# CameraController.net
KiCad netlist of a schematic drawn in EAGLE
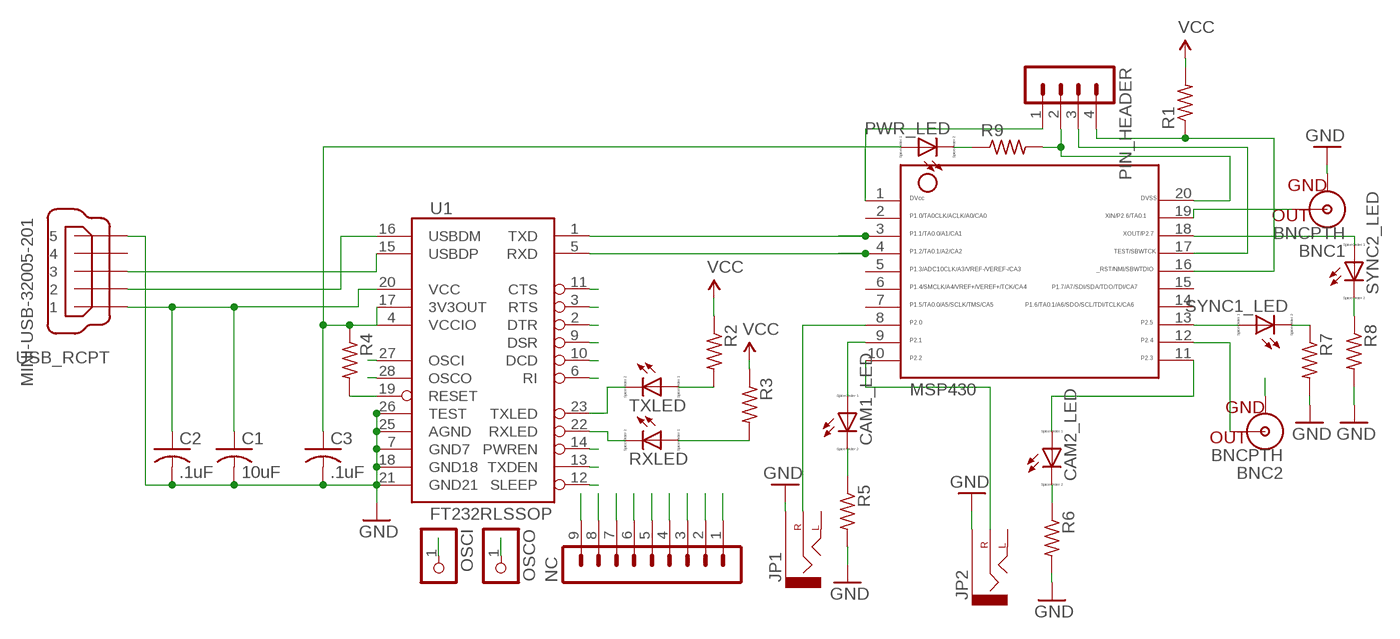
[diagram p0: schematic, sheet 1]

(export (version "E")
  (design (tool "Eeschema 10.0.6"))
  (components
    (comp (ref "BNC1")
      (value "BNCPTH")
      (footprint "eagle-import:BNC")
      (libsource (lib "eagle-import") (part "BNCPTH"))
    )
    (comp (ref "BNC2")
      (value "BNCPTH")
      (footprint "eagle-import:BNC")
      (libsource (lib "eagle-import") (part "BNCPTH"))
    )
    (comp (ref "C1")
      (value "10uF")
      (footprint "eagle-import:C0805")
      (libsource (lib "eagle-import") (part "C-USC0805"))
    )
    (comp (ref "C2")
      (value ".1uF")
      (footprint "eagle-import:C0603")
      (libsource (lib "eagle-import") (part "C-USC0603"))
    )
    (comp (ref "C3")
      (value ".1uF")
      (footprint "eagle-import:C0603")
      (libsource (lib "eagle-import") (part "C-USC0603"))
    )
    (comp (ref "CAM1_LED")
      (value "LED_E")
      (footprint "eagle-import:LED_1206")
      (libsource (lib "eagle-import") (part "LED_E"))
    )
    (comp (ref "CAM2_LED")
      (value "LED_E")
      (footprint "eagle-import:LED_1206")
      (libsource (lib "eagle-import") (part "LED_E"))
    )
    (comp (ref "JP1")
      (value "AUDIO-JACKPTH")
      (footprint "eagle-import:AUDIO-JACK")
      (libsource (lib "eagle-import") (part "AUDIO-JACKPTH"))
    )
    (comp (ref "JP2")
      (value "AUDIO-JACKPTH")
      (footprint "eagle-import:AUDIO-JACK")
      (libsource (lib "eagle-import") (part "AUDIO-JACKPTH"))
    )
    (comp (ref "MSP430")
      (value "MSP430")
      (footprint "eagle-import:20_PIN")
      (libsource (lib "eagle-import") (part "MSP430"))
    )
    (comp (ref "NC")
      (value "MA09-1")
      (footprint "eagle-import:MA09-1")
      (libsource (lib "eagle-import") (part "MA09-1"))
    )
    (comp (ref "OSCI")
      (value "PINHD-1X1")
      (footprint "eagle-import:1X01")
      (libsource (lib "eagle-import") (part "PINHD-1X1"))
    )
    (comp (ref "OSCO")
      (value "PINHD-1X1")
      (footprint "eagle-import:1X01")
      (libsource (lib "eagle-import") (part "PINHD-1X1"))
    )
    (comp (ref "PIN_HEADER")
      (value "MA04-1")
      (footprint "eagle-import:MA04-1")
      (libsource (lib "eagle-import") (part "MA04-1"))
    )
    (comp (ref "PWR_LED")
      (value "LED_E")
      (footprint "eagle-import:LED_1206")
      (libsource (lib "eagle-import") (part "LED_E"))
    )
    (comp (ref "R1")
      (value "R-US_R1206")
      (footprint "eagle-import:R1206")
      (libsource (lib "eagle-import") (part "R-US_R1206"))
    )
    (comp (ref "R2")
      (value "R-US_R1206")
      (footprint "eagle-import:R1206")
      (libsource (lib "eagle-import") (part "R-US_R1206"))
    )
    (comp (ref "R3")
      (value "R-US_R1206")
      (footprint "eagle-import:R1206")
      (libsource (lib "eagle-import") (part "R-US_R1206"))
    )
    (comp (ref "R4")
      (value "R-US_R1206")
      (footprint "eagle-import:R1206")
      (libsource (lib "eagle-import") (part "R-US_R1206"))
    )
    (comp (ref "R5")
      (value "R-US_R1206")
      (footprint "eagle-import:R1206")
      (libsource (lib "eagle-import") (part "R-US_R1206"))
    )
    (comp (ref "R6")
      (value "R-US_R1206")
      (footprint "eagle-import:R1206")
      (libsource (lib "eagle-import") (part "R-US_R1206"))
    )
    (comp (ref "R7")
      (value "R-US_R1206")
      (footprint "eagle-import:R1206")
      (libsource (lib "eagle-import") (part "R-US_R1206"))
    )
    (comp (ref "R8")
      (value "R-US_R1206")
      (footprint "eagle-import:R1206")
      (libsource (lib "eagle-import") (part "R-US_R1206"))
    )
    (comp (ref "R9")
      (value "R-US_R1206")
      (footprint "eagle-import:R1206")
      (libsource (lib "eagle-import") (part "R-US_R1206"))
    )
    (comp (ref "RXLED")
      (value "LED_E")
      (footprint "eagle-import:LED_1206")
      (libsource (lib "eagle-import") (part "LED_E"))
    )
    (comp (ref "SYNC1_LED")
      (value "LED_E")
      (footprint "eagle-import:LED_1206")
      (libsource (lib "eagle-import") (part "LED_E"))
    )
    (comp (ref "SYNC2_LED")
      (value "LED_E")
      (footprint "eagle-import:LED_1206")
      (libsource (lib "eagle-import") (part "LED_E"))
    )
    (comp (ref "TXLED")
      (value "LED_E")
      (footprint "eagle-import:LED_1206")
      (libsource (lib "eagle-import") (part "LED_E"))
    )
    (comp (ref "U1")
      (value "FT232RLSSOP")
      (footprint "eagle-import:SSOP28DB")
      (libsource (lib "eagle-import") (part "FT232RLSSOP"))
    )
    (comp (ref "USB_RCPT")
      (value "MINI-USB-32005-201")
      (footprint "eagle-import:32005-201")
      (libsource (lib "eagle-import") (part "MINI-USB-32005-201"))
    )
  )
  (nets
    (net (code "1") (name "/CTS") (class "Default")
      (node (ref "NC") (pin "4") (pinfunction "4_4") (pintype "passive"))
      (node (ref "U1") (pin "11") (pinfunction "CTS_11") (pintype "input"))
    )
    (net (code "2") (name "/DCD") (class "Default")
      (node (ref "NC") (pin "5") (pinfunction "5_5") (pintype "passive"))
      (node (ref "U1") (pin "10") (pinfunction "DCD_10") (pintype "input"))
    )
    (net (code "3") (name "/DSR") (class "Default")
      (node (ref "NC") (pin "6") (pinfunction "6_6") (pintype "passive"))
      (node (ref "U1") (pin "9") (pinfunction "DSR_9") (pintype "input"))
    )
    (net (code "4") (name "/DTR") (class "Default")
      (node (ref "NC") (pin "9") (pinfunction "9_9") (pintype "passive"))
      (node (ref "U1") (pin "2") (pinfunction "DTR_2") (pintype "output"))
    )
    (net (code "5") (name "/OSCI") (class "Default")
      (node (ref "OSCI") (pin "1") (pinfunction "1_1") (pintype "passive"))
      (node (ref "U1") (pin "27") (pinfunction "OSCI_27") (pintype "input"))
    )
    (net (code "6") (name "/OSCO") (class "Default")
      (node (ref "OSCO") (pin "1") (pinfunction "1_1") (pintype "passive"))
      (node (ref "U1") (pin "28") (pinfunction "OSCO_28") (pintype "output"))
    )
    (net (code "7") (name "/PWREN") (class "Default")
      (node (ref "NC") (pin "1") (pinfunction "1_1") (pintype "passive"))
      (node (ref "U1") (pin "14") (pinfunction "PWREN_14") (pintype "input"))
    )
    (net (code "8") (name "/RI") (class "Default")
      (node (ref "NC") (pin "7") (pinfunction "7_7") (pintype "passive"))
      (node (ref "U1") (pin "6") (pinfunction "RI_6") (pintype "input"))
    )
    (net (code "9") (name "/RTS") (class "Default")
      (node (ref "NC") (pin "8") (pinfunction "8_8") (pintype "passive"))
      (node (ref "U1") (pin "3") (pinfunction "RTS_3") (pintype "output"))
    )
    (net (code "10") (name "/SLEEP") (class "Default")
      (node (ref "NC") (pin "3") (pinfunction "3_3") (pintype "passive"))
      (node (ref "U1") (pin "12") (pinfunction "SLEEP_12") (pintype "input"))
    )
    (net (code "11") (name "/TXDEN") (class "Default")
      (node (ref "NC") (pin "2") (pinfunction "2_2") (pintype "passive"))
      (node (ref "U1") (pin "13") (pinfunction "TXDEN_13") (pintype "input"))
    )
    (net (code "12") (name "GND") (class "Default")
      (node (ref "BNC1") (pin "GND") (pinfunction "GND_GND") (pintype "bidirectional"))
      (node (ref "BNC2") (pin "GND") (pinfunction "GND_GND") (pintype "bidirectional"))
      (node (ref "C1") (pin "2") (pinfunction "2_2") (pintype "passive"))
      (node (ref "C2") (pin "2") (pinfunction "2_2") (pintype "passive"))
      (node (ref "C3") (pin "2") (pinfunction "2_2") (pintype "passive"))
      (node (ref "JP1") (pin "SLEEVE") (pinfunction "SLEEVE_SLEEVE") (pintype "bidirectional"))
      (node (ref "JP2") (pin "SLEEVE") (pinfunction "SLEEVE_SLEEVE") (pintype "bidirectional"))
      (node (ref "MSP430") (pin "20") (pinfunction "20_20") (pintype "bidirectional"))
      (node (ref "PIN_HEADER") (pin "2") (pinfunction "2_2") (pintype "passive"))
      (node (ref "R5") (pin "2") (pinfunction "2_2") (pintype "passive"))
      (node (ref "R6") (pin "2") (pinfunction "2_2") (pintype "passive"))
      (node (ref "R7") (pin "2") (pinfunction "2_2") (pintype "passive"))
      (node (ref "R8") (pin "2") (pinfunction "2_2") (pintype "passive"))
      (node (ref "R9") (pin "2") (pinfunction "2_2") (pintype "passive"))
      (node (ref "U1") (pin "18") (pinfunction "GND18_18") (pintype "power_in"))
      (node (ref "U1") (pin "21") (pinfunction "GND21_21") (pintype "power_in"))
      (node (ref "U1") (pin "25") (pinfunction "AGND_25") (pintype "power_in"))
      (node (ref "U1") (pin "26") (pinfunction "TEST_26") (pintype "input"))
      (node (ref "U1") (pin "7") (pinfunction "GND7_7") (pintype "power_in"))
      (node (ref "USB_RCPT") (pin "5") (pinfunction "5_5") (pintype "passive"))
    )
    (net (code "13") (name "Net-(BNC1-OUT)") (class "Default")
      (node (ref "BNC1") (pin "S") (pinfunction "OUT_S") (pintype "bidirectional"))
      (node (ref "MSP430") (pin "19") (pinfunction "19_19") (pintype "bidirectional"))
    )
    (net (code "14") (name "Net-(BNC2-OUT)") (class "Default")
      (node (ref "BNC2") (pin "S") (pinfunction "OUT_S") (pintype "bidirectional"))
      (node (ref "MSP430") (pin "12") (pinfunction "12_12") (pintype "bidirectional"))
    )
    (net (code "15") (name "Net-(CAM1_LED-PadA)") (class "Default")
      (node (ref "CAM1_LED") (pin "A") (pinfunction "A_A") (pintype "passive"))
      (node (ref "MSP430") (pin "9") (pinfunction "9_9") (pintype "bidirectional"))
    )
    (net (code "16") (name "Net-(CAM1_LED-PadC)") (class "Default")
      (node (ref "CAM1_LED") (pin "C") (pinfunction "C_C") (pintype "passive"))
      (node (ref "R5") (pin "1") (pinfunction "1_1") (pintype "passive"))
    )
    (net (code "17") (name "Net-(CAM2_LED-PadA)") (class "Default")
      (node (ref "CAM2_LED") (pin "A") (pinfunction "A_A") (pintype "passive"))
      (node (ref "MSP430") (pin "11") (pinfunction "11_11") (pintype "bidirectional"))
    )
    (net (code "18") (name "Net-(CAM2_LED-PadC)") (class "Default")
      (node (ref "CAM2_LED") (pin "C") (pinfunction "C_C") (pintype "passive"))
      (node (ref "R6") (pin "1") (pinfunction "1_1") (pintype "passive"))
    )
    (net (code "19") (name "Net-(JP1-RIGHT)") (class "Default")
      (node (ref "JP1") (pin "RING") (pinfunction "RIGHT_RING") (pintype "bidirectional"))
      (node (ref "MSP430") (pin "8") (pinfunction "8_8") (pintype "bidirectional"))
    )
    (net (code "20") (name "Net-(JP2-RIGHT)") (class "Default")
      (node (ref "JP2") (pin "RING") (pinfunction "RIGHT_RING") (pintype "bidirectional"))
      (node (ref "MSP430") (pin "10") (pinfunction "10_10") (pintype "bidirectional"))
    )
    (net (code "21") (name "Net-(MSP430-Pad13)") (class "Default")
      (node (ref "MSP430") (pin "13") (pinfunction "13_13") (pintype "bidirectional"))
      (node (ref "SYNC1_LED") (pin "A") (pinfunction "A_A") (pintype "passive"))
    )
    (net (code "22") (name "Net-(MSP430-Pad16)") (class "Default")
      (node (ref "MSP430") (pin "16") (pinfunction "16_16") (pintype "bidirectional"))
      (node (ref "PIN_HEADER") (pin "4") (pinfunction "4_4") (pintype "passive"))
      (node (ref "R1") (pin "1") (pinfunction "1_1") (pintype "passive"))
    )
    (net (code "23") (name "Net-(MSP430-Pad17)") (class "Default")
      (node (ref "MSP430") (pin "17") (pinfunction "17_17") (pintype "bidirectional"))
      (node (ref "PIN_HEADER") (pin "3") (pinfunction "3_3") (pintype "passive"))
    )
    (net (code "24") (name "Net-(MSP430-Pad18)") (class "Default")
      (node (ref "MSP430") (pin "18") (pinfunction "18_18") (pintype "bidirectional"))
      (node (ref "SYNC2_LED") (pin "A") (pinfunction "A_A") (pintype "passive"))
    )
    (net (code "25") (name "Net-(PWR_LED-PadC)") (class "Default")
      (node (ref "PWR_LED") (pin "C") (pinfunction "C_C") (pintype "passive"))
      (node (ref "R9") (pin "1") (pinfunction "1_1") (pintype "passive"))
    )
    (net (code "26") (name "Net-(R2-Pad2)") (class "Default")
      (node (ref "R2") (pin "2") (pinfunction "2_2") (pintype "passive"))
      (node (ref "TXLED") (pin "A") (pinfunction "A_A") (pintype "passive"))
    )
    (net (code "27") (name "Net-(R3-Pad2)") (class "Default")
      (node (ref "R3") (pin "2") (pinfunction "2_2") (pintype "passive"))
      (node (ref "RXLED") (pin "A") (pinfunction "A_A") (pintype "passive"))
    )
    (net (code "28") (name "Net-(R7-Pad1)") (class "Default")
      (node (ref "R7") (pin "1") (pinfunction "1_1") (pintype "passive"))
      (node (ref "SYNC1_LED") (pin "C") (pinfunction "C_C") (pintype "passive"))
    )
    (net (code "29") (name "Net-(R8-Pad1)") (class "Default")
      (node (ref "R8") (pin "1") (pinfunction "1_1") (pintype "passive"))
      (node (ref "SYNC2_LED") (pin "C") (pinfunction "C_C") (pintype "passive"))
    )
    (net (code "30") (name "Net-(U1-3V3OUT)") (class "Default")
      (node (ref "C3") (pin "1") (pinfunction "1_1") (pintype "passive"))
      (node (ref "MSP430") (pin "1") (pinfunction "1_1") (pintype "bidirectional"))
      (node (ref "PIN_HEADER") (pin "1") (pinfunction "1_1") (pintype "passive"))
      (node (ref "PWR_LED") (pin "A") (pinfunction "A_A") (pintype "passive"))
      (node (ref "R4") (pin "1") (pinfunction "1_1") (pintype "passive"))
      (node (ref "U1") (pin "17") (pinfunction "3V3OUT_17") (pintype "output"))
      (node (ref "U1") (pin "4") (pinfunction "VCCIO_4") (pintype "power_in"))
    )
    (net (code "31") (name "Net-(U1-RESET)") (class "Default")
      (node (ref "R4") (pin "2") (pinfunction "2_2") (pintype "passive"))
      (node (ref "U1") (pin "19") (pinfunction "RESET_19") (pintype "input"))
    )
    (net (code "32") (name "Net-(U1-RXD)") (class "Default")
      (node (ref "MSP430") (pin "4") (pinfunction "4_4") (pintype "bidirectional"))
      (node (ref "U1") (pin "5") (pinfunction "RXD_5") (pintype "input"))
    )
    (net (code "33") (name "Net-(U1-RXLED)") (class "Default")
      (node (ref "RXLED") (pin "C") (pinfunction "C_C") (pintype "passive"))
      (node (ref "U1") (pin "22") (pinfunction "RXLED_22") (pintype "input"))
    )
    (net (code "34") (name "Net-(U1-TXD)") (class "Default")
      (node (ref "MSP430") (pin "3") (pinfunction "3_3") (pintype "bidirectional"))
      (node (ref "U1") (pin "1") (pinfunction "TXD_1") (pintype "output"))
    )
    (net (code "35") (name "Net-(U1-TXLED)") (class "Default")
      (node (ref "TXLED") (pin "C") (pinfunction "C_C") (pintype "passive"))
      (node (ref "U1") (pin "23") (pinfunction "TXLED_23") (pintype "input"))
    )
    (net (code "36") (name "Net-(U1-USBDM)") (class "Default")
      (node (ref "U1") (pin "16") (pinfunction "USBDM_16") (pintype "bidirectional"))
      (node (ref "USB_RCPT") (pin "2") (pinfunction "2_2") (pintype "passive"))
    )
    (net (code "37") (name "Net-(U1-USBDP)") (class "Default")
      (node (ref "U1") (pin "15") (pinfunction "USBDP_15") (pintype "bidirectional"))
      (node (ref "USB_RCPT") (pin "3") (pinfunction "3_3") (pintype "passive"))
    )
    (net (code "38") (name "VCC") (class "Default")
      (node (ref "C1") (pin "1") (pinfunction "1_1") (pintype "passive"))
      (node (ref "C2") (pin "1") (pinfunction "1_1") (pintype "passive"))
      (node (ref "R1") (pin "2") (pinfunction "2_2") (pintype "passive"))
      (node (ref "R2") (pin "1") (pinfunction "1_1") (pintype "passive"))
      (node (ref "R3") (pin "1") (pinfunction "1_1") (pintype "passive"))
      (node (ref "U1") (pin "20") (pinfunction "VCC_20") (pintype "power_in"))
      (node (ref "USB_RCPT") (pin "1") (pinfunction "1_1") (pintype "passive"))
    )
    (net (code "39") (name "unconnected-(JP1-LEFT-PadTIP)") (class "Default")
      (node (ref "JP1") (pin "TIP") (pinfunction "LEFT_TIP") (pintype "bidirectional"))
    )
    (net (code "40") (name "unconnected-(JP2-LEFT-PadTIP)") (class "Default")
      (node (ref "JP2") (pin "TIP") (pinfunction "LEFT_TIP") (pintype "bidirectional"))
    )
    (net (code "41") (name "unconnected-(MSP430-Pad2)") (class "Default")
      (node (ref "MSP430") (pin "2") (pinfunction "2_2") (pintype "bidirectional"))
    )
    (net (code "42") (name "unconnected-(MSP430-Pad5)") (class "Default")
      (node (ref "MSP430") (pin "5") (pinfunction "5_5") (pintype "bidirectional"))
    )
    (net (code "43") (name "unconnected-(MSP430-Pad6)") (class "Default")
      (node (ref "MSP430") (pin "6") (pinfunction "6_6") (pintype "bidirectional"))
    )
    (net (code "44") (name "unconnected-(MSP430-Pad7)") (class "Default")
      (node (ref "MSP430") (pin "7") (pinfunction "7_7") (pintype "bidirectional"))
    )
    (net (code "45") (name "unconnected-(MSP430-Pad14)") (class "Default")
      (node (ref "MSP430") (pin "14") (pinfunction "14_14") (pintype "bidirectional"))
    )
    (net (code "46") (name "unconnected-(MSP430-Pad15)") (class "Default")
      (node (ref "MSP430") (pin "15") (pinfunction "15_15") (pintype "bidirectional"))
    )
    (net (code "47") (name "unconnected-(USB_RCPT-Pad4)") (class "Default")
      (node (ref "USB_RCPT") (pin "4") (pinfunction "4_4") (pintype "passive"))
    )
  )
)
